# FT2232HL_IN.net
KiCad netlist of a schematic drawn in Altium Designer
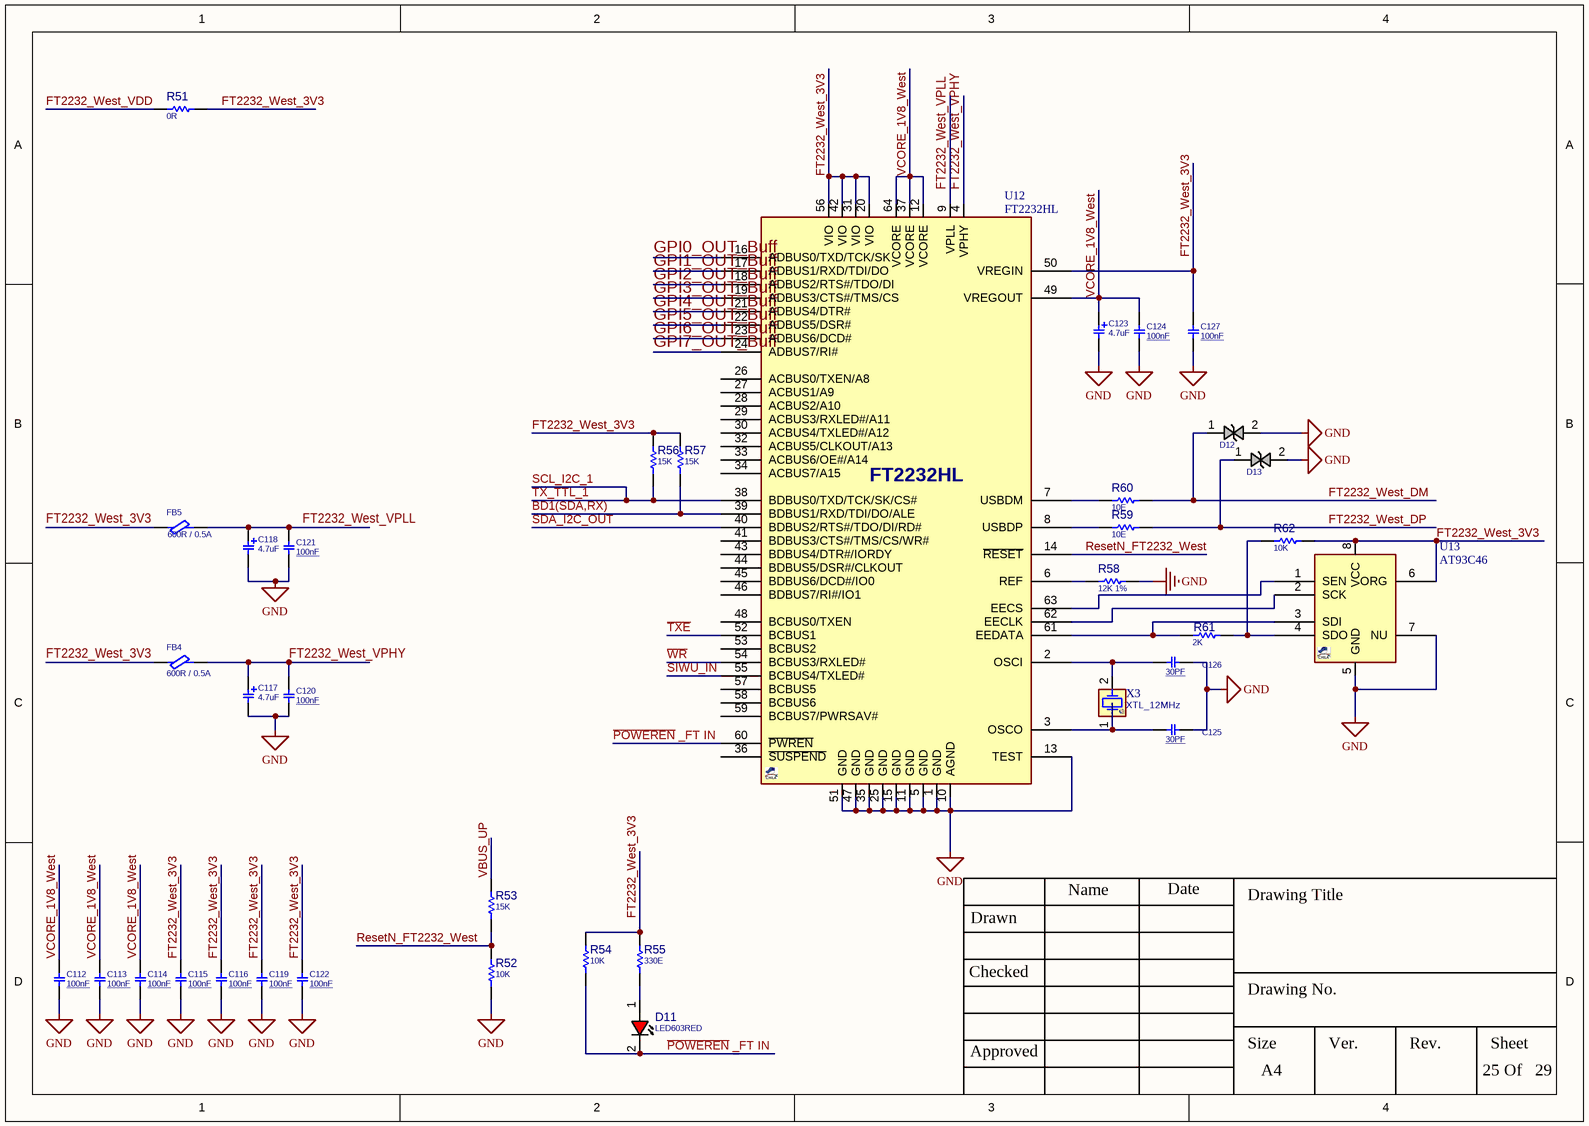
[diagram p0: FT2232HL_IN.SchDoc]

(export (version "E")
  (design (tool "Eeschema 10.0.6"))
  (components
    (comp (ref "C112")
      (value "100nF")
      (footprint "0603")
      (description "CAP, FILM, 1uF, 16V, Acryl, 20%, 1210")
      (fields (field (name "MANF_P#") "ECP-U1C105MA5") (field (name "MANF") "Panasonic"))
      (libsource (lib "cap_film_smd_passive") (part "CAP_SMD_FILM_1u16v_1210"))
    )
    (comp (ref "C113")
      (value "100nF")
      (footprint "0603")
      (description "CAP, FILM, 1uF, 16V, Acryl, 20%, 1210")
      (fields (field (name "MANF_P#") "ECP-U1C105MA5") (field (name "MANF") "Panasonic"))
      (libsource (lib "cap_film_smd_passive") (part "CAP_SMD_FILM_1u16v_1210"))
    )
    (comp (ref "C114")
      (value "100nF")
      (footprint "0603")
      (description "CAP, FILM, 1uF, 16V, Acryl, 20%, 1210")
      (fields (field (name "MANF_P#") "ECP-U1C105MA5") (field (name "MANF") "Panasonic"))
      (libsource (lib "cap_film_smd_passive") (part "CAP_SMD_FILM_1u16v_1210"))
    )
    (comp (ref "C115")
      (value "100nF")
      (footprint "0603")
      (description "CAP, FILM, 1uF, 16V, Acryl, 20%, 1210")
      (fields (field (name "MANF_P#") "ECP-U1C105MA5") (field (name "MANF") "Panasonic"))
      (libsource (lib "cap_film_smd_passive") (part "CAP_SMD_FILM_1u16v_1210"))
    )
    (comp (ref "C116")
      (value "100nF")
      (footprint "0603")
      (description "CAP, FILM, 1uF, 16V, Acryl, 20%, 1210")
      (fields (field (name "MANF_P#") "ECP-U1C105MA5") (field (name "MANF") "Panasonic"))
      (libsource (lib "cap_film_smd_passive") (part "CAP_SMD_FILM_1u16v_1210"))
    )
    (comp (ref "C117")
      (value "4.7uF")
      (footprint "C_TN_3216")
      (description "CAP, SMD, TAN")
      (fields (field (name "MANF") "VISHAY") (field (name "MANF_P#") "T55A106M6R3C0300"))
      (libsource (lib "CapTantal_passive") (part "CAP_SMD_TAN_10uF_6.3V"))
    )
    (comp (ref "C118")
      (value "4.7uF")
      (footprint "C_TN_3216")
      (description "CAP, SMD, TAN")
      (fields (field (name "MANF") "VISHAY") (field (name "MANF_P#") "T55A106M6R3C0300"))
      (libsource (lib "CapTantal_passive") (part "CAP_SMD_TAN_10uF_6.3V"))
    )
    (comp (ref "C119")
      (value "100nF")
      (footprint "0603")
      (description "CAP, FILM, 1uF, 16V, Acryl, 20%, 1210")
      (fields (field (name "MANF_P#") "ECP-U1C105MA5") (field (name "MANF") "Panasonic"))
      (libsource (lib "cap_film_smd_passive") (part "CAP_SMD_FILM_1u16v_1210"))
    )
    (comp (ref "C120")
      (value "100nF")
      (footprint "0603")
      (description "CAP, FILM, 1uF, 16V, Acryl, 20%, 1210")
      (fields (field (name "MANF_P#") "ECP-U1C105MA5") (field (name "MANF") "Panasonic"))
      (libsource (lib "cap_film_smd_passive") (part "CAP_SMD_FILM_1u16v_1210"))
    )
    (comp (ref "C121")
      (value "100nF")
      (footprint "0603")
      (description "CAP, FILM, 1uF, 16V, Acryl, 20%, 1210")
      (fields (field (name "MANF_P#") "ECP-U1C105MA5") (field (name "MANF") "Panasonic"))
      (libsource (lib "cap_film_smd_passive") (part "CAP_SMD_FILM_1u16v_1210"))
    )
    (comp (ref "C122")
      (value "100nF")
      (footprint "0603")
      (description "CAP, FILM, 1uF, 16V, Acryl, 20%, 1210")
      (fields (field (name "MANF_P#") "ECP-U1C105MA5") (field (name "MANF") "Panasonic"))
      (libsource (lib "cap_film_smd_passive") (part "CAP_SMD_FILM_1u16v_1210"))
    )
    (comp (ref "C123")
      (value "4.7uF")
      (footprint "C_TN_3216")
      (description "CAP, SMD, TAN")
      (fields (field (name "MANF") "VISHAY") (field (name "MANF_P#") "T55A106M6R3C0300"))
      (libsource (lib "CapTantal_passive") (part "CAP_SMD_TAN_10uF_6.3V"))
    )
    (comp (ref "C124")
      (value "100nF")
      (footprint "0603")
      (description "CAP, FILM, 1uF, 16V, Acryl, 20%, 1210")
      (fields (field (name "MANF_P#") "ECP-U1C105MA5") (field (name "MANF") "Panasonic"))
      (libsource (lib "cap_film_smd_passive") (part "CAP_SMD_FILM_1u16v_1210"))
    )
    (comp (ref "C125")
      (value "30PF")
      (footprint "C0805")
      (description "CAP, MLCC, 1nF, 50V, C0G, 10%, 0402")
      (fields (field (name "MANF") "Murata"))
      (libsource (lib "mlcc_smd_passive") (part "CAP_SMD_MLCC"))
    )
    (comp (ref "C126")
      (value "30PF")
      (footprint "C0805")
      (description "CAP, MLCC, 1nF, 50V, C0G, 10%, 0402")
      (fields (field (name "MANF") "Murata"))
      (libsource (lib "mlcc_smd_passive") (part "CAP_SMD_MLCC"))
    )
    (comp (ref "C127")
      (value "100nF")
      (footprint "0603")
      (description "CAP, FILM, 1uF, 16V, Acryl, 20%, 1210")
      (fields (field (name "MANF_P#") "ECP-U1C105MA5") (field (name "MANF") "Panasonic"))
      (libsource (lib "cap_film_smd_passive") (part "CAP_SMD_FILM_1u16v_1210"))
    )
    (comp (ref "D11")
      (value "LED603RED")
      (footprint "LED0603RED")
      (description "LED, SMD, 0603, RED")
      (fields (field (name "MANF") "MANF") (field (name "MANF_P#") "MANF_PART#"))
      (libsource (lib "led(diode)") (part "LED_SMD_0603_RED"))
    )
    (comp (ref "D12")
      (value "TVS603")
      (footprint "D0603")
      (description "TVS, ESD PROTECT, 24VDC, Bidirectional")
      (fields (field (name "MANF_P#") "PGB0010603MR") (field (name "MANF") "LittelFuse"))
      (libsource (lib "protect_tvs_esd_fuse") (part "TVS_PGB0010603MR"))
    )
    (comp (ref "D13")
      (value "TVS603")
      (footprint "D0603")
      (description "TVS, ESD PROTECT, 24VDC, Bidirectional")
      (fields (field (name "MANF_P#") "PGB0010603MR") (field (name "MANF") "LittelFuse"))
      (libsource (lib "protect_tvs_esd_fuse") (part "TVS_PGB0010603MR"))
    )
    (comp (ref "FB4")
      (value "600R / 0.5A")
      (footprint "L0603")
      (description "FERRITE_Bead, 0603, 0.8A, 300mOhm, 1000@100MHz")
      (fields (field (name "MANF") "TDK") (field (name "MANF_P#") "MPZ1608S102ATA00"))
      (libsource (lib "emi_filter") (part "FBEAD_SMD_MPZ1608S102"))
    )
    (comp (ref "FB5")
      (value "600R / 0.5A")
      (footprint "L0603")
      (description "FERRITE_Bead, 0603, 0.8A, 300mOhm, 1000@100MHz")
      (fields (field (name "MANF") "TDK") (field (name "MANF_P#") "MPZ1608S102ATA00"))
      (libsource (lib "emi_filter") (part "FBEAD_SMD_MPZ1608S102"))
    )
    (comp (ref "R51")
      (value "0R")
      (footprint "R0603")
      (description "RESISTOR, SMD")
      (libsource (lib "passive_smd") (part "RES_SMD_0603"))
    )
    (comp (ref "R52")
      (value "10K")
      (footprint "R0603")
      (description "RESISTOR, SMD")
      (libsource (lib "passive_smd") (part "RES_SMD_0603"))
    )
    (comp (ref "R53")
      (value "15K")
      (footprint "R0603")
      (description "RESISTOR, SMD")
      (libsource (lib "passive_smd") (part "RES_SMD_0603"))
    )
    (comp (ref "R54")
      (value "10K")
      (footprint "R0603")
      (description "RESISTOR, SMD")
      (libsource (lib "passive_smd") (part "RES_SMD_0603"))
    )
    (comp (ref "R55")
      (value "330E")
      (footprint "R0603")
      (description "RESISTOR, SMD")
      (libsource (lib "passive_smd") (part "RES_SMD_0603"))
    )
    (comp (ref "R56")
      (value "15K")
      (footprint "R0603")
      (description "RESISTOR, SMD")
      (libsource (lib "passive_smd") (part "RES_SMD_0603"))
    )
    (comp (ref "R57")
      (value "15K")
      (footprint "R0603")
      (description "RESISTOR, SMD")
      (libsource (lib "passive_smd") (part "RES_SMD_0603"))
    )
    (comp (ref "R58")
      (value "12K 1%")
      (footprint "R025W_AX04")
      (description "RESISTOR, THD")
      (fields (field (name "MANF_P#") "RK73H1ETTP4701F") (field (name "MANF") "KOA SPEER"))
      (libsource (lib "passive_thd") (part "RES_THD"))
    )
    (comp (ref "R59")
      (value "10E")
      (footprint "R0603")
      (description "RESISTOR, SMD")
      (libsource (lib "passive_smd") (part "RES_SMD_0603"))
    )
    (comp (ref "R60")
      (value "10E")
      (footprint "R0603")
      (description "RESISTOR, SMD")
      (libsource (lib "passive_smd") (part "RES_SMD_0603"))
    )
    (comp (ref "R61")
      (value "2K")
      (footprint "R025W_AX04")
      (description "RESISTOR, THD")
      (fields (field (name "MANF_P#") "RK73H1ETTP4701F") (field (name "MANF") "KOA SPEER"))
      (libsource (lib "passive_thd") (part "RES_THD"))
    )
    (comp (ref "R62")
      (value "10K")
      (footprint "R025W_AX04")
      (description "RESISTOR, THD")
      (fields (field (name "MANF_P#") "RK73H1ETTP4701F") (field (name "MANF") "KOA SPEER"))
      (libsource (lib "passive_thd") (part "RES_THD"))
    )
    (comp (ref "U12")
      (value "FT2232HL")
      (footprint "QFG50_64")
      (description "USB, DUAL, Multipurpose UART/FIFO, USB High Speed")
      (fields (field (name "MANF") "FTDI"))
      (libsource (lib "usbic") (part "FT2232HL_QFP64"))
    )
    (comp (ref "U13")
      (value "AT93C46")
      (footprint "SO_8")
      (description "EEPROM, SPI, 1KBIT, SOP-8")
      (libsource (lib "memory_eeprom_SPI") (part "EEPROM_SPI_AT93C46_SOP8"))
    )
    (comp (ref "X3")
      (value "XTL_12MHz")
      (footprint "XTL_2_11X5")
      (description "Crystal MOST POPULAR ABL HC49 PACKAGE")
      (fields (field (name "MANF") "ABRACON") (field (name "MANF_P#") "ABLS-8.000MHZ-B4-T"))
      (libsource (lib "crystal") (part "XTL_2_HC49_8MHz_SMD"))
    )
  )
  (nets
    (net (code "1") (name "/BD1(SDA,RX)") (class "Default")
      (node (ref "R57") (pin "2") (pinfunction "2_2") (pintype "passive"))
      (node (ref "U12") (pin "39") (pinfunction "BDBUS1/RXD/TDI/DO/ALE_39") (pintype "passive"))
    )
    (net (code "2") (name "/FT2232_West_3V3") (class "Default")
      (node (ref "C115") (pin "1") (pinfunction "1_1") (pintype "passive"))
      (node (ref "C116") (pin "1") (pinfunction "1_1") (pintype "passive"))
      (node (ref "C119") (pin "1") (pinfunction "1_1") (pintype "passive"))
      (node (ref "C122") (pin "1") (pinfunction "1_1") (pintype "passive"))
      (node (ref "C127") (pin "1") (pinfunction "1_1") (pintype "passive"))
      (node (ref "FB4") (pin "1") (pinfunction "1_1") (pintype "passive"))
      (node (ref "FB5") (pin "1") (pinfunction "1_1") (pintype "passive"))
      (node (ref "R51") (pin "2") (pinfunction "2_2") (pintype "passive"))
      (node (ref "R54") (pin "1") (pinfunction "1_1") (pintype "passive"))
      (node (ref "R55") (pin "1") (pinfunction "1_1") (pintype "passive"))
      (node (ref "R56") (pin "1") (pinfunction "1_1") (pintype "passive"))
      (node (ref "R57") (pin "1") (pinfunction "1_1") (pintype "passive"))
      (node (ref "R62") (pin "1") (pinfunction "1_1") (pintype "passive"))
      (node (ref "U12") (pin "20") (pinfunction "VIO_20") (pintype "passive"))
      (node (ref "U12") (pin "31") (pinfunction "VIO_31") (pintype "passive"))
      (node (ref "U12") (pin "42") (pinfunction "VIO_42") (pintype "passive"))
      (node (ref "U12") (pin "50") (pinfunction "VREGIN_50") (pintype "passive"))
      (node (ref "U12") (pin "56") (pinfunction "VIO_56") (pintype "passive"))
      (node (ref "U13") (pin "6") (pinfunction "ORG_6") (pintype "passive"))
      (node (ref "U13") (pin "8") (pinfunction "VCC_8") (pintype "passive"))
    )
    (net (code "3") (name "/FT2232_West_DM") (class "Default")
      (node (ref "D12") (pin "1") (pinfunction "1_1") (pintype "passive"))
      (node (ref "R60") (pin "1") (pinfunction "1_1") (pintype "passive"))
    )
    (net (code "4") (name "/FT2232_West_DP") (class "Default")
      (node (ref "D13") (pin "1") (pinfunction "1_1") (pintype "passive"))
      (node (ref "R59") (pin "1") (pinfunction "1_1") (pintype "passive"))
    )
    (net (code "5") (name "/FT2232_West_VDD") (class "Default")
      (node (ref "R51") (pin "1") (pinfunction "1_1") (pintype "passive"))
    )
    (net (code "6") (name "/FT2232_West_VPHY") (class "Default")
      (node (ref "C117") (pin "1") (pinfunction "1_1") (pintype "passive"))
      (node (ref "C120") (pin "1") (pinfunction "1_1") (pintype "passive"))
      (node (ref "FB4") (pin "2") (pinfunction "2_2") (pintype "passive"))
      (node (ref "U12") (pin "4") (pinfunction "VPHY_4") (pintype "passive"))
    )
    (net (code "7") (name "/FT2232_West_VPLL") (class "Default")
      (node (ref "C118") (pin "1") (pinfunction "1_1") (pintype "passive"))
      (node (ref "C121") (pin "1") (pinfunction "1_1") (pintype "passive"))
      (node (ref "FB5") (pin "2") (pinfunction "2_2") (pintype "passive"))
      (node (ref "U12") (pin "9") (pinfunction "VPLL_9") (pintype "passive"))
    )
    (net (code "8") (name "/GPI0_OUT_Buff") (class "Default")
      (node (ref "U12") (pin "16") (pinfunction "ADBUS0/TXD/TCK/SK_16") (pintype "passive"))
    )
    (net (code "9") (name "/GPI1_OUT_Buff") (class "Default")
      (node (ref "U12") (pin "17") (pinfunction "ADBUS1/RXD/TDI/DO_17") (pintype "passive"))
    )
    (net (code "10") (name "/GPI2_OUT_Buff") (class "Default")
      (node (ref "U12") (pin "18") (pinfunction "ADBUS2/RTS#/TDO/DI_18") (pintype "passive"))
    )
    (net (code "11") (name "/GPI3_OUT_Buff") (class "Default")
      (node (ref "U12") (pin "19") (pinfunction "ADBUS3/CTS#/TMS/CS_19") (pintype "passive"))
    )
    (net (code "12") (name "/GPI4_OUT_Buff") (class "Default")
      (node (ref "U12") (pin "21") (pinfunction "ADBUS4/DTR#_21") (pintype "passive"))
    )
    (net (code "13") (name "/GPI5_OUT_Buff") (class "Default")
      (node (ref "U12") (pin "22") (pinfunction "ADBUS5/DSR#_22") (pintype "passive"))
    )
    (net (code "14") (name "/GPI6_OUT_Buff") (class "Default")
      (node (ref "U12") (pin "23") (pinfunction "ADBUS6/DCD#_23") (pintype "passive"))
    )
    (net (code "15") (name "/GPI7_OUT_Buff") (class "Default")
      (node (ref "U12") (pin "24") (pinfunction "ADBUS7/RI#_24") (pintype "passive"))
    )
    (net (code "16") (name "/ResetN_FT2232_West") (class "Default")
      (node (ref "R52") (pin "1") (pinfunction "1_1") (pintype "passive"))
      (node (ref "R53") (pin "2") (pinfunction "2_2") (pintype "passive"))
      (node (ref "U12") (pin "14") (pinfunction "~{RESET}_14") (pintype "passive"))
    )
    (net (code "17") (name "/SCL_I2C_1") (class "Default")
      (node (ref "R56") (pin "2") (pinfunction "2_2") (pintype "passive"))
      (node (ref "U12") (pin "38") (pinfunction "BDBUS0/TXD/TCK/SK/CS#_38") (pintype "passive"))
    )
    (net (code "18") (name "/SDA_I2C_OUT") (class "Default")
      (node (ref "U12") (pin "40") (pinfunction "BDBUS2/RTS#/TDO/DI/RD#_40") (pintype "passive"))
    )
    (net (code "19") (name "/SIWU_IN") (class "Default")
      (node (ref "U12") (pin "55") (pinfunction "BCBUS4/TXLED#_55") (pintype "passive"))
    )
    (net (code "20") (name "/VBUS_UP") (class "Default")
      (node (ref "R53") (pin "1") (pinfunction "1_1") (pintype "passive"))
    )
    (net (code "21") (name "/VCORE_1V8_West") (class "Default")
      (node (ref "C112") (pin "1") (pinfunction "1_1") (pintype "passive"))
      (node (ref "C113") (pin "1") (pinfunction "1_1") (pintype "passive"))
      (node (ref "C114") (pin "1") (pinfunction "1_1") (pintype "passive"))
      (node (ref "C123") (pin "1") (pinfunction "1_1") (pintype "passive"))
      (node (ref "C124") (pin "1") (pinfunction "1_1") (pintype "passive"))
      (node (ref "U12") (pin "12") (pinfunction "VCORE_12") (pintype "passive"))
      (node (ref "U12") (pin "37") (pinfunction "VCORE_37") (pintype "passive"))
      (node (ref "U12") (pin "49") (pinfunction "VREGOUT_49") (pintype "passive"))
      (node (ref "U12") (pin "64") (pinfunction "VCORE_64") (pintype "passive"))
    )
    (net (code "22") (name "/~{POWEREN} _FT IN") (class "Default")
      (node (ref "D11") (pin "2") (pinfunction "CATHODE_2") (pintype "passive"))
      (node (ref "R54") (pin "2") (pinfunction "2_2") (pintype "passive"))
      (node (ref "U12") (pin "60") (pinfunction "~{PWREN}_60") (pintype "passive"))
    )
    (net (code "23") (name "/~{TXE}") (class "Default")
      (node (ref "U12") (pin "52") (pinfunction "BCBUS1_52") (pintype "passive"))
    )
    (net (code "24") (name "/~{WR}") (class "Default")
      (node (ref "U12") (pin "54") (pinfunction "BCBUS3/RXLED#_54") (pintype "passive"))
    )
    (net (code "25") (name "GND") (class "Default")
      (node (ref "C112") (pin "2") (pinfunction "2_2") (pintype "passive"))
      (node (ref "C113") (pin "2") (pinfunction "2_2") (pintype "passive"))
      (node (ref "C114") (pin "2") (pinfunction "2_2") (pintype "passive"))
      (node (ref "C115") (pin "2") (pinfunction "2_2") (pintype "passive"))
      (node (ref "C116") (pin "2") (pinfunction "2_2") (pintype "passive"))
      (node (ref "C117") (pin "2") (pinfunction "2_2") (pintype "passive"))
      (node (ref "C118") (pin "2") (pinfunction "2_2") (pintype "passive"))
      (node (ref "C119") (pin "2") (pinfunction "2_2") (pintype "passive"))
      (node (ref "C120") (pin "2") (pinfunction "2_2") (pintype "passive"))
      (node (ref "C121") (pin "2") (pinfunction "2_2") (pintype "passive"))
      (node (ref "C122") (pin "2") (pinfunction "2_2") (pintype "passive"))
      (node (ref "C123") (pin "2") (pinfunction "2_2") (pintype "passive"))
      (node (ref "C124") (pin "2") (pinfunction "2_2") (pintype "passive"))
      (node (ref "C125") (pin "2") (pinfunction "2_2") (pintype "passive"))
      (node (ref "C126") (pin "2") (pinfunction "2_2") (pintype "passive"))
      (node (ref "C127") (pin "2") (pinfunction "2_2") (pintype "passive"))
      (node (ref "D12") (pin "2") (pinfunction "2_2") (pintype "passive"))
      (node (ref "D13") (pin "2") (pinfunction "2_2") (pintype "passive"))
      (node (ref "R52") (pin "2") (pinfunction "2_2") (pintype "passive"))
      (node (ref "R58") (pin "1") (pinfunction "1_1") (pintype "passive"))
      (node (ref "U12") (pin "1") (pinfunction "GND_1") (pintype "passive"))
      (node (ref "U12") (pin "10") (pinfunction "AGND_10") (pintype "passive"))
      (node (ref "U12") (pin "11") (pinfunction "GND_11") (pintype "passive"))
      (node (ref "U12") (pin "13") (pinfunction "TEST_13") (pintype "passive"))
      (node (ref "U12") (pin "15") (pinfunction "GND_15") (pintype "passive"))
      (node (ref "U12") (pin "25") (pinfunction "GND_25") (pintype "passive"))
      (node (ref "U12") (pin "35") (pinfunction "GND_35") (pintype "passive"))
      (node (ref "U12") (pin "47") (pinfunction "GND_47") (pintype "passive"))
      (node (ref "U12") (pin "5") (pinfunction "GND_5") (pintype "passive"))
      (node (ref "U12") (pin "51") (pinfunction "GND_51") (pintype "passive"))
      (node (ref "U13") (pin "5") (pinfunction "GND_5") (pintype "passive"))
      (node (ref "U13") (pin "7") (pinfunction "NU_7") (pintype "passive"))
    )
    (net (code "26") (name "Net-(D11-ANODE)") (class "Default")
      (node (ref "D11") (pin "1") (pinfunction "ANODE_1") (pintype "passive"))
      (node (ref "R55") (pin "2") (pinfunction "2_2") (pintype "passive"))
    )
    (net (code "27") (name "Net-(U12-EECLK)") (class "Default")
      (node (ref "U12") (pin "62") (pinfunction "EECLK_62") (pintype "passive"))
      (node (ref "U13") (pin "2") (pinfunction "SCK_2") (pintype "passive"))
    )
    (net (code "28") (name "Net-(U12-EECS)") (class "Default")
      (node (ref "U12") (pin "63") (pinfunction "EECS_63") (pintype "passive"))
      (node (ref "U13") (pin "1") (pinfunction "SEN_1") (pintype "passive"))
    )
    (net (code "29") (name "Net-(U12-EEDATA)") (class "Default")
      (node (ref "R61") (pin "2") (pinfunction "2_2") (pintype "passive"))
      (node (ref "U12") (pin "61") (pinfunction "EEDATA_61") (pintype "passive"))
      (node (ref "U13") (pin "3") (pinfunction "SDI_3") (pintype "passive"))
    )
    (net (code "30") (name "Net-(U12-OSCI)") (class "Default")
      (node (ref "C126") (pin "1") (pinfunction "1_1") (pintype "passive"))
      (node (ref "U12") (pin "2") (pinfunction "OSCI_2") (pintype "passive"))
      (node (ref "X3") (pin "2") (pinfunction "OSC2_2") (pintype "passive"))
    )
    (net (code "31") (name "Net-(U12-OSCO)") (class "Default")
      (node (ref "C125") (pin "1") (pinfunction "1_1") (pintype "passive"))
      (node (ref "U12") (pin "3") (pinfunction "OSCO_3") (pintype "passive"))
      (node (ref "X3") (pin "1") (pinfunction "OSC1_1") (pintype "passive"))
    )
    (net (code "32") (name "Net-(U12-REF)") (class "Default")
      (node (ref "R58") (pin "2") (pinfunction "2_2") (pintype "passive"))
      (node (ref "U12") (pin "6") (pinfunction "REF_6") (pintype "passive"))
    )
    (net (code "33") (name "Net-(U12-USBDM)") (class "Default")
      (node (ref "R60") (pin "2") (pinfunction "2_2") (pintype "passive"))
      (node (ref "U12") (pin "7") (pinfunction "USBDM_7") (pintype "passive"))
    )
    (net (code "34") (name "Net-(U12-USBDP)") (class "Default")
      (node (ref "R59") (pin "2") (pinfunction "2_2") (pintype "passive"))
      (node (ref "U12") (pin "8") (pinfunction "USBDP_8") (pintype "passive"))
    )
    (net (code "35") (name "Net-(U13-SDO)") (class "Default")
      (node (ref "R61") (pin "1") (pinfunction "1_1") (pintype "passive"))
      (node (ref "R62") (pin "2") (pinfunction "2_2") (pintype "passive"))
      (node (ref "U13") (pin "4") (pinfunction "SDO_4") (pintype "passive"))
    )
    (net (code "36") (name "unconnected-(U12-ACBUS0{slash}TXEN{slash}A8-Pad26)") (class "Default")
      (node (ref "U12") (pin "26") (pinfunction "ACBUS0/TXEN/A8_26") (pintype "passive"))
    )
    (net (code "37") (name "unconnected-(U12-ACBUS1{slash}A9-Pad27)") (class "Default")
      (node (ref "U12") (pin "27") (pinfunction "ACBUS1/A9_27") (pintype "passive"))
    )
    (net (code "38") (name "unconnected-(U12-ACBUS2{slash}A10-Pad28)") (class "Default")
      (node (ref "U12") (pin "28") (pinfunction "ACBUS2/A10_28") (pintype "passive"))
    )
    (net (code "39") (name "unconnected-(U12-ACBUS3{slash}RXLED#{slash}A11-Pad29)") (class "Default")
      (node (ref "U12") (pin "29") (pinfunction "ACBUS3/RXLED#/A11_29") (pintype "passive"))
    )
    (net (code "40") (name "unconnected-(U12-ACBUS4{slash}TXLED#{slash}A12-Pad30)") (class "Default")
      (node (ref "U12") (pin "30") (pinfunction "ACBUS4/TXLED#/A12_30") (pintype "passive"))
    )
    (net (code "41") (name "unconnected-(U12-ACBUS5{slash}CLKOUT{slash}A13-Pad32)") (class "Default")
      (node (ref "U12") (pin "32") (pinfunction "ACBUS5/CLKOUT/A13_32") (pintype "passive"))
    )
    (net (code "42") (name "unconnected-(U12-ACBUS6{slash}OE#{slash}A14-Pad33)") (class "Default")
      (node (ref "U12") (pin "33") (pinfunction "ACBUS6/OE#/A14_33") (pintype "passive"))
    )
    (net (code "43") (name "unconnected-(U12-ACBUS7{slash}A15-Pad34)") (class "Default")
      (node (ref "U12") (pin "34") (pinfunction "ACBUS7/A15_34") (pintype "passive"))
    )
    (net (code "44") (name "unconnected-(U12-BCBUS0{slash}TXEN-Pad48)") (class "Default")
      (node (ref "U12") (pin "48") (pinfunction "BCBUS0/TXEN_48") (pintype "passive"))
    )
    (net (code "45") (name "unconnected-(U12-BCBUS2-Pad53)") (class "Default")
      (node (ref "U12") (pin "53") (pinfunction "BCBUS2_53") (pintype "passive"))
    )
    (net (code "46") (name "unconnected-(U12-BCBUS5-Pad57)") (class "Default")
      (node (ref "U12") (pin "57") (pinfunction "BCBUS5_57") (pintype "passive"))
    )
    (net (code "47") (name "unconnected-(U12-BCBUS6-Pad58)") (class "Default")
      (node (ref "U12") (pin "58") (pinfunction "BCBUS6_58") (pintype "passive"))
    )
    (net (code "48") (name "unconnected-(U12-BCBUS7{slash}PWRSAV#-Pad59)") (class "Default")
      (node (ref "U12") (pin "59") (pinfunction "BCBUS7/PWRSAV#_59") (pintype "passive"))
    )
    (net (code "49") (name "unconnected-(U12-BDBUS3{slash}CTS#{slash}TMS{slash}CS{slash}WR#-Pad41)") (class "Default")
      (node (ref "U12") (pin "41") (pinfunction "BDBUS3/CTS#/TMS/CS/WR#_41") (pintype "passive"))
    )
    (net (code "50") (name "unconnected-(U12-BDBUS4{slash}DTR#{slash}IORDY-Pad43)") (class "Default")
      (node (ref "U12") (pin "43") (pinfunction "BDBUS4/DTR#/IORDY_43") (pintype "passive"))
    )
    (net (code "51") (name "unconnected-(U12-BDBUS5{slash}DSR#{slash}CLKOUT-Pad44)") (class "Default")
      (node (ref "U12") (pin "44") (pinfunction "BDBUS5/DSR#/CLKOUT_44") (pintype "passive"))
    )
    (net (code "52") (name "unconnected-(U12-BDBUS6{slash}DCD#{slash}IO0-Pad45)") (class "Default")
      (node (ref "U12") (pin "45") (pinfunction "BDBUS6/DCD#/IO0_45") (pintype "passive"))
    )
    (net (code "53") (name "unconnected-(U12-BDBUS7{slash}RI#{slash}IO1-Pad46)") (class "Default")
      (node (ref "U12") (pin "46") (pinfunction "BDBUS7/RI#/IO1_46") (pintype "passive"))
    )
    (net (code "54") (name "unconnected-(U12-~{SUSPEND}-Pad36)") (class "Default")
      (node (ref "U12") (pin "36") (pinfunction "~{SUSPEND}_36") (pintype "passive"))
    )
  )
)
